# test_2.net
KiCad netlist of a schematic drawn in EasyEDA
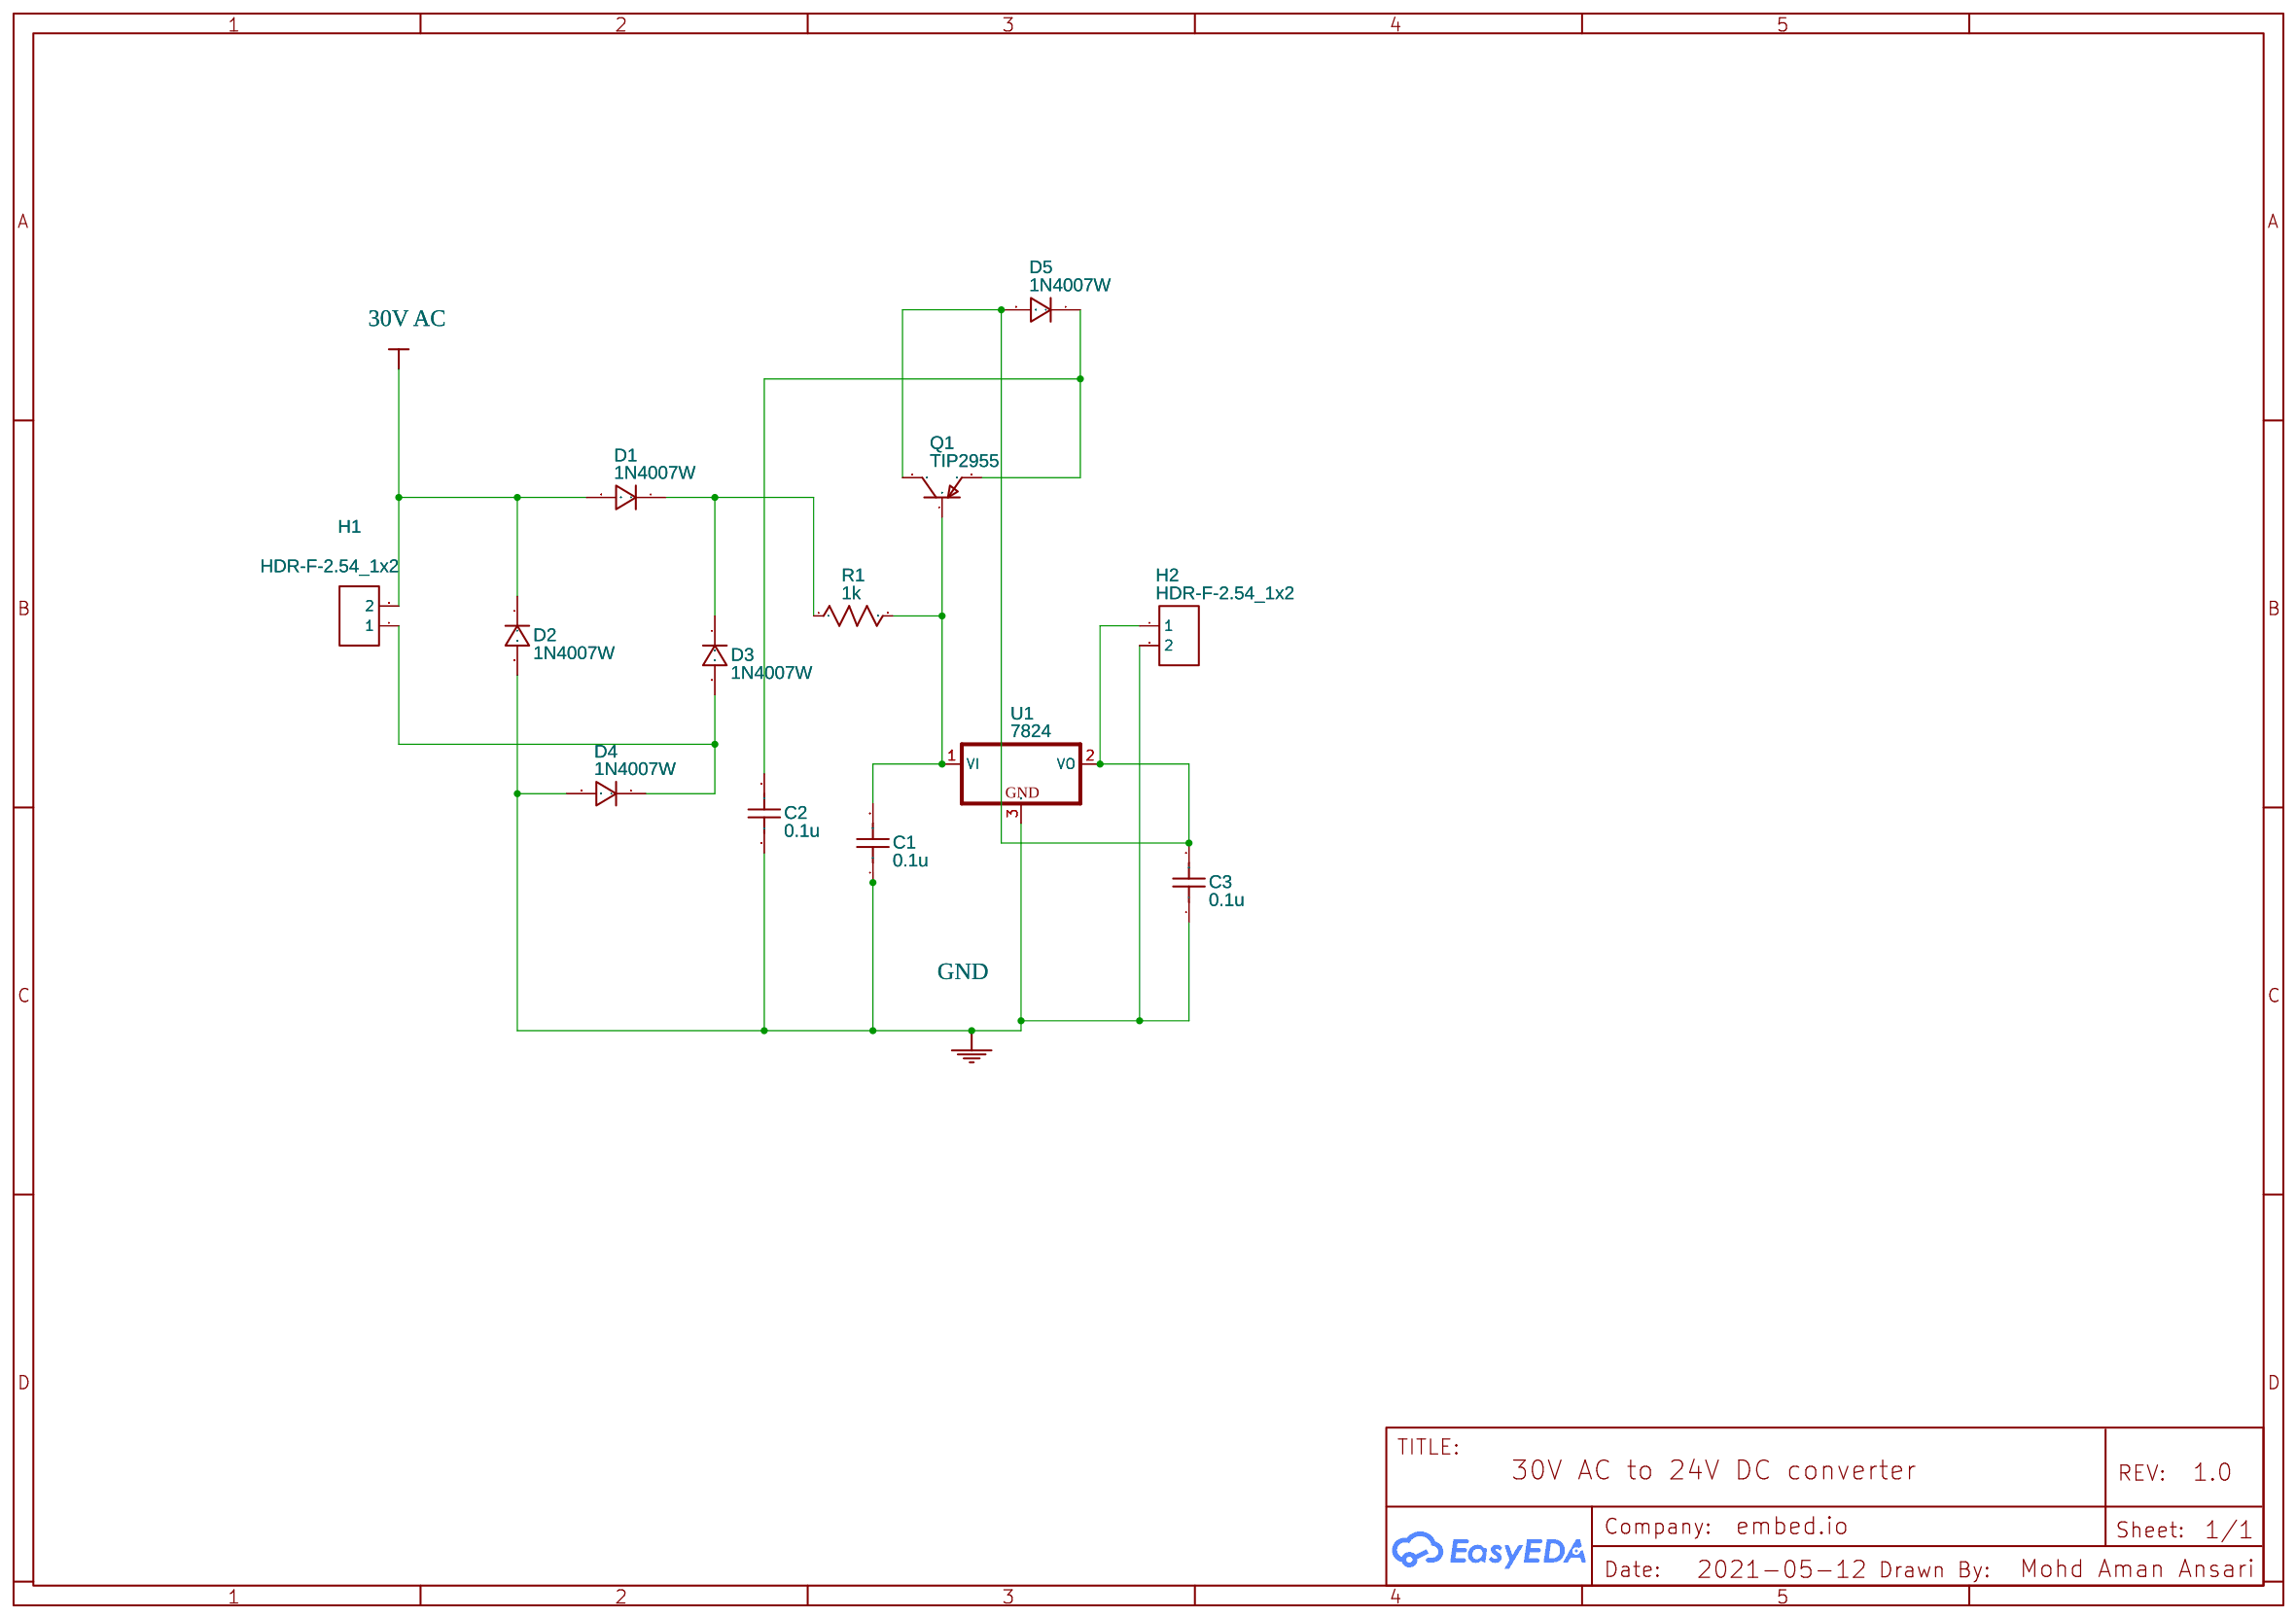
[diagram p0: schematic sheet]

(export (version "E")
  (design (tool "Eeschema 10.0.6"))
  (components
    (comp (ref "C1") (value "0.1u") (libsource (lib "") (part "C_0603_US")))
    (comp (ref "C2") (value "0.1u") (libsource (lib "") (part "C_0603_US")))
    (comp (ref "C3") (value "0.1u") (libsource (lib "") (part "C_0603_US")))
    (comp (ref "D1")
      (value "1N4007W")
      (fields (field (name "BOM_Supplier Part") "C328592"))
      (libsource (lib "") (part "1N4007W"))
    )
    (comp (ref "D2")
      (value "1N4007W")
      (fields (field (name "BOM_Supplier Part") "C328592"))
      (libsource (lib "") (part "1N4007W_1"))
    )
    (comp (ref "D3")
      (value "1N4007W")
      (fields (field (name "BOM_Supplier Part") "C328592"))
      (libsource (lib "") (part "1N4007W_1"))
    )
    (comp (ref "D4")
      (value "1N4007W")
      (fields (field (name "BOM_Supplier Part") "C328592"))
      (libsource (lib "") (part "1N4007W"))
    )
    (comp (ref "D5")
      (value "1N4007W")
      (fields (field (name "BOM_Supplier Part") "C328592"))
      (libsource (lib "") (part "1N4007W"))
    )
    (comp (ref "H1")
      (value "HDR-F-2.54_1x2")
      (fields (field (name "BOM_Supplier Part") "C49661"))
      (libsource (lib "") (part "HDR-F-2.54_1x2"))
    )
    (comp (ref "H2")
      (value "HDR-F-2.54_1x2")
      (fields (field (name "BOM_Supplier Part") "C49661"))
      (libsource (lib "") (part "HDR-F-2.54_1x2_1"))
    )
    (comp (ref "Q1")
      (value "TIP2955")
      (fields (field (name "BOM_Supplier Part") "C262991"))
      (libsource (lib "") (part "TIP2955"))
    )
    (comp (ref "R1") (value "1k") (libsource (lib "") (part "R_0603_US")))
    (comp (ref "U1") (value "7824") (libsource (lib "") (part "7824")))
  )
  (nets
    (net (code "1") (name "30V AC") (class "Default")
      (node (ref "D1") (pin "2") (pinfunction "2_2") (pintype "unspecified"))
      (node (ref "D2") (pin "1") (pinfunction "1_1") (pintype "unspecified"))
      (node (ref "H1") (pin "2") (pinfunction "2_2") (pintype "input"))
    )
    (net (code "2") (name "GND") (class "Default")
      (node (ref "C1") (pin "1") (pinfunction "1_1") (pintype "unspecified"))
      (node (ref "C2") (pin "1") (pinfunction "1_1") (pintype "unspecified"))
      (node (ref "C3") (pin "1") (pinfunction "1_1") (pintype "unspecified"))
      (node (ref "D2") (pin "2") (pinfunction "2_2") (pintype "unspecified"))
      (node (ref "D4") (pin "2") (pinfunction "2_2") (pintype "unspecified"))
      (node (ref "H2") (pin "2") (pinfunction "2_2") (pintype "input"))
      (node (ref "U1") (pin "3") (pinfunction "GND_3") (pintype "unspecified"))
    )
    (net (code "3") (name "Net-(D1-Pad1)") (class "Default")
      (node (ref "D1") (pin "1") (pinfunction "1_1") (pintype "unspecified"))
      (node (ref "D3") (pin "1") (pinfunction "1_1") (pintype "unspecified"))
      (node (ref "R1") (pin "1") (pinfunction "1_1") (pintype "unspecified"))
    )
    (net (code "4") (name "Net-(D3-Pad2)") (class "Default")
      (node (ref "D3") (pin "2") (pinfunction "2_2") (pintype "unspecified"))
      (node (ref "D4") (pin "1") (pinfunction "1_1") (pintype "unspecified"))
      (node (ref "H1") (pin "1") (pinfunction "1_1") (pintype "input"))
    )
    (net (code "5") (name "Net-(Q1-B)") (class "Default")
      (node (ref "C1") (pin "2") (pinfunction "2_2") (pintype "unspecified"))
      (node (ref "Q1") (pin "1") (pinfunction "B_1") (pintype "unspecified"))
      (node (ref "R1") (pin "2") (pinfunction "2_2") (pintype "unspecified"))
      (node (ref "U1") (pin "1") (pinfunction "VI_1") (pintype "input"))
    )
    (net (code "6") (name "Net-(Q1-C)") (class "Default")
      (node (ref "C3") (pin "2") (pinfunction "2_2") (pintype "unspecified"))
      (node (ref "D5") (pin "2") (pinfunction "2_2") (pintype "unspecified"))
      (node (ref "H2") (pin "1") (pinfunction "1_1") (pintype "input"))
      (node (ref "Q1") (pin "2") (pinfunction "C_2") (pintype "unspecified"))
      (node (ref "U1") (pin "2") (pinfunction "VO_2") (pintype "unspecified"))
    )
    (net (code "7") (name "Net-(Q1-E)") (class "Default")
      (node (ref "C2") (pin "2") (pinfunction "2_2") (pintype "unspecified"))
      (node (ref "D5") (pin "1") (pinfunction "1_1") (pintype "unspecified"))
      (node (ref "Q1") (pin "3") (pinfunction "E_3") (pintype "unspecified"))
    )
  )
)
